# Tartarus_Joystick_Mod_M0_IO.net
KiCad netlist of a schematic drawn in Altium Designer
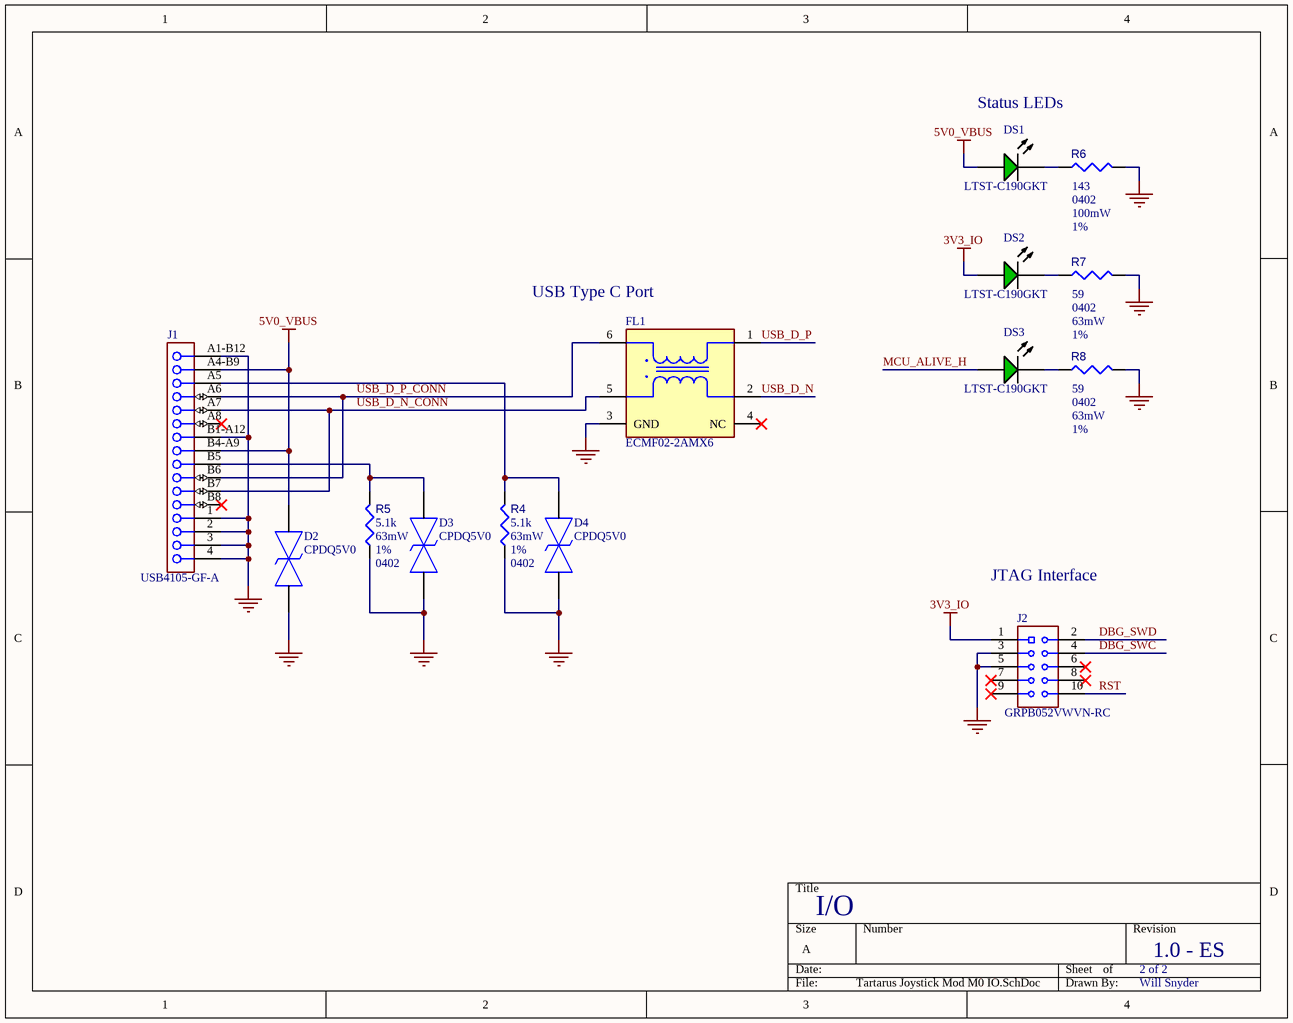
[diagram p0: Tartarus Joystick Mod M0 IO.SchDoc]

(export (version "E")
  (design (tool "Eeschema 10.0.6"))
  (components
    (comp (ref "D2")
      (value "CPDQ5V0")
      (footprint "MBTB-D-SOD-923F-IMP-0402")
      (description "18.6V Clamp 9.4A (8/20Âµs) Ipp Tvs Diode Surface Mount 0402/SOD-923F")
      (fields (field (name "MF") "Comchip Technology") (field (name "MP") "CPDQ5V0-HF"))
      (libsource (lib "Personal Workspace") (part "CPDQ5V0-HF"))
    )
    (comp (ref "D3")
      (value "CPDQ5V0")
      (footprint "MBTB-D-SOD-923F-IMP-0402")
      (description "18.6V Clamp 9.4A (8/20Âµs) Ipp Tvs Diode Surface Mount 0402/SOD-923F")
      (fields (field (name "MF") "Comchip Technology") (field (name "MP") "CPDQ5V0-HF"))
      (libsource (lib "Personal Workspace") (part "CPDQ5V0-HF"))
    )
    (comp (ref "D4")
      (value "CPDQ5V0")
      (footprint "MBTB-D-SOD-923F-IMP-0402")
      (description "18.6V Clamp 9.4A (8/20Âµs) Ipp Tvs Diode Surface Mount 0402/SOD-923F")
      (fields (field (name "MF") "Comchip Technology") (field (name "MP") "CPDQ5V0-HF"))
      (libsource (lib "Personal Workspace") (part "CPDQ5V0-HF"))
    )
    (comp (ref "DS1")
      (value "LTST-C190GKT")
      (footprint "LTST-C190GKT_V")
      (description "LED Uni-Color Green, 100 mW, 30 mA, -55 to 85 degC, 2-Pin SMD, RoHS, Tape and Reel")
      (fields (field (name "POWER") "100mW") (field (name "MANUFACTURER") "Lite-On"))
      (libsource (lib "Personal Workspace") (part "LED-GREEN-AK-2"))
    )
    (comp (ref "DS2")
      (value "LTST-C190GKT")
      (footprint "LTST-C190GKT_V")
      (description "LED Uni-Color Green, 100 mW, 30 mA, -55 to 85 degC, 2-Pin SMD, RoHS, Tape and Reel")
      (fields (field (name "POWER") "100mW") (field (name "MANUFACTURER") "Lite-On"))
      (libsource (lib "Personal Workspace") (part "LED-GREEN-AK-2"))
    )
    (comp (ref "DS3")
      (value "LTST-C190GKT")
      (footprint "LTST-C190GKT_V")
      (description "LED Uni-Color Green, 100 mW, 30 mA, -55 to 85 degC, 2-Pin SMD, RoHS, Tape and Reel")
      (fields (field (name "POWER") "100mW") (field (name "MANUFACTURER") "Lite-On"))
      (libsource (lib "Personal Workspace") (part "LED-GREEN-AK-2"))
    )
    (comp (ref "FL1")
      (value "ECMF02-2AMX6")
      (footprint "FP-QFN-6L-IPC_A")
      (description "Data Line Filter, 2 Function(s), 6 Pin(s), Plastic")
      (libsource (lib "Personal Workspace") (part "8feffc7f24acfb857157da90e949b57"))
    )
    (comp (ref "J1")
      (value "USB4105-GF-A")
      (footprint "FP-USB4105-GF-A-MFG")
      (description "Conn USB 2.0 Type C RCP 24 POS 0.3mm/0.5mm Solder RA SMD 24 Terminal 1 Port T/R")
      (libsource (lib "Personal Workspace") (part "USB4105-GF-A"))
    )
    (comp (ref "J2")
      (value "GRPB052VWVN-RC")
      (footprint "SULLINS_GRPB052VWVN-RC")
      (description "Connector Header Through Hole 10 position 0.050 (1.27mm)")
      (fields (field (name "MF") "Sullins"))
      (libsource (lib "Personal Workspace") (part "GRPB052VWVN-RC"))
    )
    (comp (ref "R4")
      (value "5.1k")
      (footprint "RESC1005X40X25NL05T05")
      (description "Fixed Resistor, Thin Film, 0.063W, 5100ohm, 50V, 1% +/-Tol, 50ppm/Cel, Surface Mount, 0402")
      (fields
        (field (name "POWER") "63mW")
        (field (name "TOLERANCE") "1%")
        (field (name "CASE/PACKAGE") "0402")
        (field (name "Comment") "MCS04020C5101FE000")
      )
      (libsource (lib "Personal Workspace") (part "RES-2"))
    )
    (comp (ref "R5")
      (value "5.1k")
      (footprint "RESC1005X40X25NL05T05")
      (description "Fixed Resistor, Thin Film, 0.063W, 5100ohm, 50V, 1% +/-Tol, 50ppm/Cel, Surface Mount, 0402")
      (fields
        (field (name "POWER") "63mW")
        (field (name "TOLERANCE") "1%")
        (field (name "CASE/PACKAGE") "0402")
        (field (name "Comment") "MCS04020C5101FE000")
      )
      (libsource (lib "Personal Workspace") (part "RES-2"))
    )
    (comp (ref "R6")
      (value "143")
      (footprint "RESC1005X40X25NL05T05")
      (fields
        (field (name "CASE/PACKAGE") "0402")
        (field (name "TOLERANCE") "1%")
        (field (name "POWER") "100mW")
        (field (name "Comment") "ERJ-2RKF1430X")
      )
      (libsource (lib "Personal Workspace") (part "RES-2"))
    )
    (comp (ref "R7")
      (value "59")
      (footprint "RESC1005X40X25NL05T05")
      (fields
        (field (name "TOLERANCE") "1%")
        (field (name "POWER") "63mW")
        (field (name "CASE/PACKAGE") "0402")
        (field (name "Comment") "CRCW040259R0FKED")
      )
      (libsource (lib "Personal Workspace") (part "RES-2"))
    )
    (comp (ref "R8")
      (value "59")
      (footprint "RESC1005X40X25NL05T05")
      (fields
        (field (name "TOLERANCE") "1%")
        (field (name "POWER") "63mW")
        (field (name "CASE/PACKAGE") "0402")
        (field (name "Comment") "CRCW040259R0FKED")
      )
      (libsource (lib "Personal Workspace") (part "RES-2"))
    )
  )
  (nets
    (net (code "1") (name "/DBG_SWC") (class "Default")
      (node (ref "J2") (pin "4") (pinfunction "4_4") (pintype "passive"))
    )
    (net (code "2") (name "/DBG_SWD") (class "Default")
      (node (ref "J2") (pin "2") (pinfunction "2_2") (pintype "passive"))
    )
    (net (code "3") (name "/MCU_ALIVE_H") (class "Default")
      (node (ref "DS3") (pin "1") (pinfunction "A_1") (pintype "passive"))
    )
    (net (code "4") (name "/RST") (class "Default")
      (node (ref "J2") (pin "10") (pinfunction "10_10") (pintype "passive"))
    )
    (net (code "5") (name "/USB_D_N") (class "Default")
      (node (ref "FL1") (pin "2") (pinfunction "D-_2") (pintype "passive"))
    )
    (net (code "6") (name "/USB_D_N_CONN") (class "Default")
      (node (ref "FL1") (pin "5") (pinfunction "D-_5") (pintype "passive"))
      (node (ref "J1") (pin "A7") (pinfunction "Dn1_A7") (pintype "bidirectional"))
      (node (ref "J1") (pin "B7") (pinfunction "Dn2_B7") (pintype "bidirectional"))
    )
    (net (code "7") (name "/USB_D_P") (class "Default")
      (node (ref "FL1") (pin "1") (pinfunction "D+_1") (pintype "passive"))
    )
    (net (code "8") (name "/USB_D_P_CONN") (class "Default")
      (node (ref "FL1") (pin "6") (pinfunction "D+_6") (pintype "passive"))
      (node (ref "J1") (pin "A6") (pinfunction "Dp1_A6") (pintype "bidirectional"))
      (node (ref "J1") (pin "B6") (pinfunction "Dp2_B6") (pintype "bidirectional"))
    )
    (net (code "9") (name "3V3_IO") (class "Default")
      (node (ref "DS2") (pin "1") (pinfunction "A_1") (pintype "passive"))
      (node (ref "J2") (pin "1") (pinfunction "1_1") (pintype "passive"))
    )
    (net (code "10") (name "5V0_VBUS") (class "Default")
      (node (ref "D2") (pin "1") (pinfunction "K_1") (pintype "passive"))
      (node (ref "DS1") (pin "1") (pinfunction "A_1") (pintype "passive"))
      (node (ref "J1") (pin "A4-B9") (pinfunction "VBUS_A4-B9") (pintype "power_in"))
      (node (ref "J1") (pin "B4-A9") (pinfunction "VBUS_B4-A9") (pintype "power_in"))
    )
    (net (code "11") (name "GND") (class "Default")
      (node (ref "D2") (pin "2") (pinfunction "A_2") (pintype "passive"))
      (node (ref "D3") (pin "2") (pinfunction "A_2") (pintype "passive"))
      (node (ref "D4") (pin "2") (pinfunction "A_2") (pintype "passive"))
      (node (ref "FL1") (pin "3") (pinfunction "GND_3") (pintype "power_in"))
      (node (ref "J1") (pin "1") (pinfunction "MNT_1_1") (pintype "power_in"))
      (node (ref "J1") (pin "2") (pinfunction "MNT_2_2") (pintype "power_in"))
      (node (ref "J1") (pin "3") (pinfunction "MNT_3_3") (pintype "power_in"))
      (node (ref "J1") (pin "4") (pinfunction "MNT_4_4") (pintype "power_in"))
      (node (ref "J1") (pin "A1-B12") (pinfunction "GND_A1-B12") (pintype "power_in"))
      (node (ref "J1") (pin "B1-A12") (pinfunction "GND_B1-A12") (pintype "power_in"))
      (node (ref "J2") (pin "3") (pinfunction "3_3") (pintype "passive"))
      (node (ref "J2") (pin "5") (pinfunction "5_5") (pintype "passive"))
      (node (ref "R4") (pin "2") (pinfunction "2_2") (pintype "passive"))
      (node (ref "R5") (pin "2") (pinfunction "2_2") (pintype "passive"))
      (node (ref "R6") (pin "2") (pinfunction "2_2") (pintype "passive"))
      (node (ref "R7") (pin "2") (pinfunction "2_2") (pintype "passive"))
      (node (ref "R8") (pin "2") (pinfunction "2_2") (pintype "passive"))
    )
    (net (code "12") (name "Net-(D3-K)") (class "Default")
      (node (ref "D3") (pin "1") (pinfunction "K_1") (pintype "passive"))
      (node (ref "J1") (pin "B5") (pinfunction "CC2_B5") (pintype "passive"))
      (node (ref "R5") (pin "1") (pinfunction "1_1") (pintype "passive"))
    )
    (net (code "13") (name "Net-(D4-K)") (class "Default")
      (node (ref "D4") (pin "1") (pinfunction "K_1") (pintype "passive"))
      (node (ref "J1") (pin "A5") (pinfunction "CC1_A5") (pintype "passive"))
      (node (ref "R4") (pin "1") (pinfunction "1_1") (pintype "passive"))
    )
    (net (code "14") (name "Net-(DS1-K)") (class "Default")
      (node (ref "DS1") (pin "2") (pinfunction "K_2") (pintype "passive"))
      (node (ref "R6") (pin "1") (pinfunction "1_1") (pintype "passive"))
    )
    (net (code "15") (name "Net-(DS2-K)") (class "Default")
      (node (ref "DS2") (pin "2") (pinfunction "K_2") (pintype "passive"))
      (node (ref "R7") (pin "1") (pinfunction "1_1") (pintype "passive"))
    )
    (net (code "16") (name "Net-(DS3-K)") (class "Default")
      (node (ref "DS3") (pin "2") (pinfunction "K_2") (pintype "passive"))
      (node (ref "R8") (pin "1") (pinfunction "1_1") (pintype "passive"))
    )
    (net (code "17") (name "unconnected-(FL1-NC-Pad4)") (class "Default")
      (node (ref "FL1") (pin "4") (pinfunction "NC_4") (pintype "passive+no_connect"))
    )
    (net (code "18") (name "unconnected-(J1-SBU1-PadA8)") (class "Default")
      (node (ref "J1") (pin "A8") (pinfunction "SBU1_A8") (pintype "bidirectional+no_connect"))
    )
    (net (code "19") (name "unconnected-(J1-SBU2-PadB8)") (class "Default")
      (node (ref "J1") (pin "B8") (pinfunction "SBU2_B8") (pintype "bidirectional+no_connect"))
    )
    (net (code "20") (name "unconnected-(J2-Pad6)") (class "Default")
      (node (ref "J2") (pin "6") (pinfunction "6_6") (pintype "passive+no_connect"))
    )
    (net (code "21") (name "unconnected-(J2-Pad7)") (class "Default")
      (node (ref "J2") (pin "7") (pinfunction "7_7") (pintype "passive+no_connect"))
    )
    (net (code "22") (name "unconnected-(J2-Pad8)") (class "Default")
      (node (ref "J2") (pin "8") (pinfunction "8_8") (pintype "passive+no_connect"))
    )
    (net (code "23") (name "unconnected-(J2-Pad9)") (class "Default")
      (node (ref "J2") (pin "9") (pinfunction "9_9") (pintype "passive+no_connect"))
    )
  )
)
